# QCopterCAM_POWER_Sch.net
KiCad netlist of a schematic drawn in Altium Designer
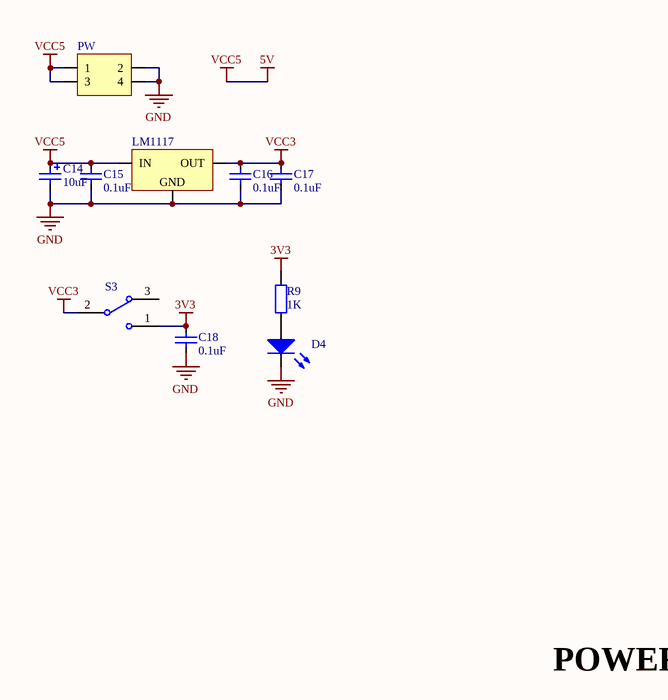
[diagram p0: QCopterCAM_POWER_Sch.SchDoc]

(export (version "E")
  (design (tool "Eeschema 10.0.6"))
  (components
    (comp (ref "C14")
      (value "10uF")
      (footprint "PCB_Passive:CAP_TAN_B1210")
      (description "Capacitor")
      (fields (field (name "Comment") "Cap_Tan_1210"))
      (libsource (lib "SCH_Passive") (part "Cap_Tan_1210"))
    )
    (comp (ref "C15")
      (value "0.1uF")
      (footprint "PCB_Passive:CAP_0603")
      (description "Capacitor")
      (fields (field (name "Comment") "Cap_0603"))
      (libsource (lib "SCH_Passive") (part "Cap_0603"))
    )
    (comp (ref "C16")
      (value "0.1uF")
      (footprint "PCB_Passive:CAP_0603")
      (description "Capacitor")
      (fields (field (name "Comment") "Cap_0603"))
      (libsource (lib "SCH_Passive") (part "Cap_0603"))
    )
    (comp (ref "C17")
      (value "0.1uF")
      (footprint "PCB_Passive:CAP_0603")
      (description "Capacitor")
      (fields (field (name "Comment") "Cap_0603"))
      (libsource (lib "SCH_Passive") (part "Cap_0603"))
    )
    (comp (ref "C18")
      (value "0.1uF")
      (footprint "PCB_Passive:CAP_0603")
      (description "Capacitor")
      (fields (field (name "Comment") "Cap_0603"))
      (libsource (lib "SCH_Passive") (part "Cap_0603"))
    )
    (comp (ref "D4")
      (value "LED_0603_BLUE")
      (footprint "PCB_Active:LED_0603_BLUE")
      (description "LED")
      (libsource (lib "SCH_Active") (part "LED_0603_BLUE"))
    )
    (comp (ref "LM1")
      (value "LM1117")
      (footprint "PCB_IC:SOT223")
      (description "Power")
      (libsource (lib "SCH_IC") (part "LM1117"))
    )
    (comp (ref "PW")
      (value "HDR2X2_90_2.54")
      (footprint "PCB_Connector:HDR2X2_90_2.54")
      (description "Header")
      (libsource (lib "SCH_Connector") (part "HDR2X2_90_2.54"))
    )
    (comp (ref "R9")
      (value "1K")
      (footprint "PCB_Passive:RES_0603")
      (description "Resistor")
      (fields (field (name "Comment") "Res_0603"))
      (libsource (lib "SCH_Passive") (part "Res_0603"))
    )
    (comp (ref "S3")
      (value "SW-SPDT")
      (footprint "PCB_Switch:SW_T")
      (description "SPDT Subminiature Toggle Switch, Right Angle Mounting, Vertical Actuation")
      (fields (field (name "PUBLISHER") "Altium Limited"))
      (libsource (lib "SCH_Switch") (part "SW-SPDT_1"))
    )
  )
  (nets
    (net (code "1") (name "3V3") (class "Default")
      (node (ref "C18") (pin "2") (pinfunction "2_2") (pintype "passive"))
      (node (ref "R9") (pin "2") (pinfunction "2_2") (pintype "passive"))
      (node (ref "S3") (pin "1") (pinfunction "1_1") (pintype "passive"))
    )
    (net (code "2") (name "5V") (class "Default")
      (node (ref "C14") (pin "1") (pinfunction "1_1") (pintype "passive"))
      (node (ref "C15") (pin "2") (pinfunction "2_2") (pintype "passive"))
      (node (ref "LM1") (pin "3") (pinfunction "IN_3") (pintype "power_in"))
      (node (ref "PW") (pin "1") (pinfunction "1_1") (pintype "passive"))
      (node (ref "PW") (pin "3") (pinfunction "3_3") (pintype "passive"))
    )
    (net (code "3") (name "GND") (class "Default")
      (node (ref "C14") (pin "2") (pinfunction "2_2") (pintype "passive"))
      (node (ref "C15") (pin "1") (pinfunction "1_1") (pintype "passive"))
      (node (ref "C16") (pin "1") (pinfunction "1_1") (pintype "passive"))
      (node (ref "C17") (pin "1") (pinfunction "1_1") (pintype "passive"))
      (node (ref "C18") (pin "1") (pinfunction "1_1") (pintype "passive"))
      (node (ref "D4") (pin "2") (pinfunction "K_2") (pintype "passive"))
      (node (ref "LM1") (pin "1") (pinfunction "GND_1") (pintype "power_in"))
      (node (ref "PW") (pin "2") (pinfunction "2_2") (pintype "passive"))
      (node (ref "PW") (pin "4") (pinfunction "4_4") (pintype "passive"))
    )
    (net (code "4") (name "Net-(D4-A)") (class "Default")
      (node (ref "D4") (pin "1") (pinfunction "A_1") (pintype "passive"))
      (node (ref "R9") (pin "1") (pinfunction "1_1") (pintype "passive"))
    )
    (net (code "5") (name "VCC3") (class "Default")
      (node (ref "C16") (pin "2") (pinfunction "2_2") (pintype "passive"))
      (node (ref "C17") (pin "2") (pinfunction "2_2") (pintype "passive"))
      (node (ref "LM1") (pin "2") (pinfunction "OUT_2") (pintype "power_in"))
      (node (ref "S3") (pin "2") (pinfunction "2_2") (pintype "passive"))
    )
    (net (code "6") (name "unconnected-(S3-Pad3)") (class "Default")
      (node (ref "S3") (pin "3") (pinfunction "3_3") (pintype "passive"))
    )
  )
)
